# mcu2.net
KiCad netlist of a schematic drawn in Altium Designer
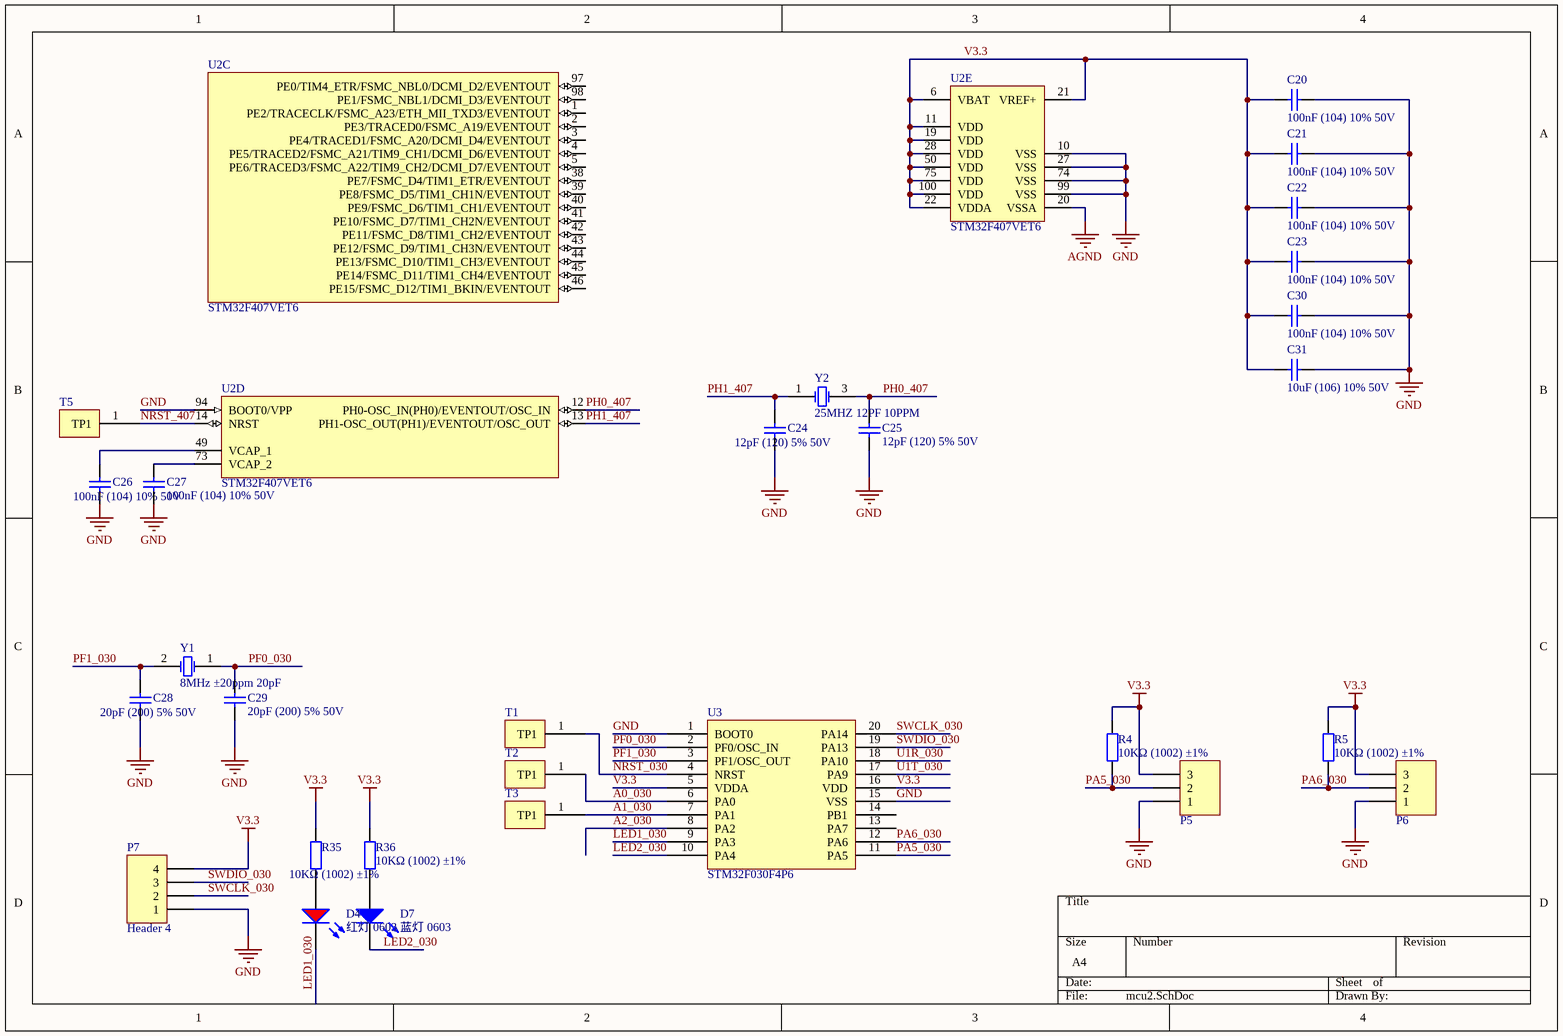
[diagram p0: mcu2.SchDoc]

(export (version "E")
  (design (tool "Eeschema 10.0.6"))
  (components
    (comp (ref "C20")
      (value "100nF (104) 10% 50V")
      (footprint "0603_C")
      (description "贴片电容")
      (libsource (lib "Miscellaneous Devices LC") (part "0603 100nF (104) 10% 50V"))
    )
    (comp (ref "C21")
      (value "100nF (104) 10% 50V")
      (footprint "0603_C")
      (description "贴片电容")
      (libsource (lib "Miscellaneous Devices LC") (part "0603 100nF (104) 10% 50V"))
    )
    (comp (ref "C22")
      (value "100nF (104) 10% 50V")
      (footprint "0603_C")
      (description "贴片电容")
      (libsource (lib "Miscellaneous Devices LC") (part "0603 100nF (104) 10% 50V"))
    )
    (comp (ref "C23")
      (value "100nF (104) 10% 50V")
      (footprint "0603_C")
      (description "贴片电容")
      (libsource (lib "Miscellaneous Devices LC") (part "0603 100nF (104) 10% 50V"))
    )
    (comp (ref "C24")
      (value "12pF (120) 5% 50V")
      (footprint "0603_C")
      (description "贴片电容")
      (libsource (lib "Miscellaneous Devices LC") (part "0603 12pF (120) 5% 50V"))
    )
    (comp (ref "C25")
      (value "12pF (120) 5% 50V")
      (footprint "0603_C")
      (description "贴片电容")
      (libsource (lib "Miscellaneous Devices LC") (part "0603 12pF (120) 5% 50V"))
    )
    (comp (ref "C26")
      (value "100nF (104) 10% 50V")
      (footprint "0603_C")
      (description "贴片电容")
      (libsource (lib "Miscellaneous Devices LC") (part "0603 100nF (104) 10% 50V"))
    )
    (comp (ref "C27")
      (value "100nF (104) 10% 50V")
      (footprint "0603_C")
      (description "贴片电容")
      (libsource (lib "Miscellaneous Devices LC") (part "0603 100nF (104) 10% 50V"))
    )
    (comp (ref "C28")
      (value "20pF (200) 5% 50V")
      (footprint "0603_C")
      (description "贴片电容")
      (libsource (lib "Miscellaneous Devices LC") (part "0603 20pF (200) 5% 50V"))
    )
    (comp (ref "C29")
      (value "20pF (200) 5% 50V")
      (footprint "0603_C")
      (description "贴片电容")
      (libsource (lib "Miscellaneous Devices LC") (part "0603 20pF (200) 5% 50V"))
    )
    (comp (ref "C30")
      (value "100nF (104) 10% 50V")
      (footprint "1206_C")
      (description "贴片电容")
      (libsource (lib "Miscellaneous Devices LC") (part "1206 100nF (104) 10% 50V"))
    )
    (comp (ref "C31")
      (value "10uF (106) 10% 50V")
      (footprint "1206_C")
      (description "贴片电容")
      (libsource (lib "Miscellaneous Devices LC") (part "1206 10uF (106) 10% 50V"))
    )
    (comp (ref "D4")
      (value "红灯 0603")
      (footprint "0603_LED_S1")
      (description "发光二极管")
      (libsource (lib "Miscellaneous Devices LC") (part "0603 红灯"))
    )
    (comp (ref "D7")
      (value "蓝灯 0603")
      (footprint "0603_LED_S1")
      (description "发光二极管")
      (libsource (lib "Miscellaneous Devices LC") (part "0603 蓝灯"))
    )
    (comp (ref "P5")
      (value "Header 3")
      (footprint "HDR1X3")
      (description "Header, 3-Pin")
      (fields (field (name "PUBLISHER") "Altium Limited"))
      (libsource (lib "Miscellaneous Connectors") (part "Header 3"))
    )
    (comp (ref "P6")
      (value "Header 3")
      (footprint "HDR1X3")
      (description "Header, 3-Pin")
      (fields (field (name "PUBLISHER") "Altium Limited"))
      (libsource (lib "Miscellaneous Connectors") (part "Header 3"))
    )
    (comp (ref "P7")
      (value "Header 4")
      (footprint "HDR1X4")
      (description "Header, 4-Pin")
      (fields (field (name "PUBLISHER") "Altium Limited"))
      (libsource (lib "Miscellaneous Connectors") (part "Header 4"))
    )
    (comp (ref "R4")
      (value "10KΩ (1002) ±1%")
      (footprint "0603_R")
      (description "贴片电阻")
      (libsource (lib "Miscellaneous Devices LC") (part "0603 10KΩ (1002) 1%"))
    )
    (comp (ref "R5")
      (value "10KΩ (1002) ±1%")
      (footprint "0603_R")
      (description "贴片电阻")
      (libsource (lib "Miscellaneous Devices LC") (part "0603 10KΩ (1002) 1%"))
    )
    (comp (ref "R35")
      (value "10KΩ (1002) ±1%")
      (footprint "0603_R")
      (description "贴片电阻")
      (libsource (lib "Miscellaneous Devices LC") (part "0603 10KΩ (1002) 1%"))
    )
    (comp (ref "R36")
      (value "10KΩ (1002) ±1%")
      (footprint "0603_R")
      (description "贴片电阻")
      (libsource (lib "Miscellaneous Devices LC") (part "0603 10KΩ (1002) 1%"))
    )
    (comp (ref "T1") (value "TP1") (footprint "TP1") (libsource (lib "CHK-I") (part "TP1")))
    (comp (ref "T2") (value "TP1") (footprint "TP1") (libsource (lib "CHK-I") (part "TP1")))
    (comp (ref "T3") (value "TP1") (footprint "TP1") (libsource (lib "CHK-I") (part "TP1")))
    (comp (ref "T5") (value "TP1") (footprint "TP1") (libsource (lib "CHK-I") (part "TP1")))
    (comp (ref "U2")
      (value "STM32F407VET6")
      (footprint "LQFP-100_14x14x05P")
      (description "ARM")
      (libsource (lib "Miscellaneous Devices LC") (part "STM32F407VET6"))
    )
    (comp (ref "U3")
      (value "STM32F030F4P6")
      (footprint "TSSOP-20")
      (description "ARM")
      (libsource (lib "Miscellaneous Devices LC") (part "STM32F030F4P6"))
    )
    (comp (ref "Y1")
      (value "8MHz ±20ppm 20pF")
      (footprint "SMD-5032_2P")
      (description "贴片晶振")
      (libsource (lib "Miscellaneous Devices LC") (part "SMD-5032_2P 8MHz 20ppm 20pF"))
    )
    (comp (ref "Y2")
      (value "25MHZ 12PF 10PPM")
      (footprint "SMD-3225_4P")
      (description "贴片晶振")
      (libsource (lib "Miscellaneous Devices LC") (part "SMD-3225_4P  25MHZ 12PF 10PPM"))
    )
  )
  (nets
    (net (code "1") (name "/A0_030") (class "Default")
      (node (ref "T2") (pin "1") (pinfunction "TP1_1") (pintype "passive"))
      (node (ref "U3") (pin "6") (pinfunction "PA0_6") (pintype "passive"))
    )
    (net (code "2") (name "/A1_030") (class "Default")
      (node (ref "T3") (pin "1") (pinfunction "TP1_1") (pintype "passive"))
      (node (ref "U3") (pin "7") (pinfunction "PA1_7") (pintype "passive"))
    )
    (net (code "3") (name "/A2_030") (class "Default")
      (node (ref "U3") (pin "8") (pinfunction "PA2_8") (pintype "passive"))
    )
    (net (code "4") (name "/LED1_030") (class "Default")
      (node (ref "D4") (pin "K") (pinfunction "K_K") (pintype "passive"))
      (node (ref "U3") (pin "9") (pinfunction "PA3_9") (pintype "passive"))
    )
    (net (code "5") (name "/LED2_030") (class "Default")
      (node (ref "D7") (pin "K") (pinfunction "K_K") (pintype "passive"))
      (node (ref "U3") (pin "10") (pinfunction "PA4_10") (pintype "passive"))
    )
    (net (code "6") (name "/NRST_030") (class "Default")
      (node (ref "T1") (pin "1") (pinfunction "TP1_1") (pintype "passive"))
      (node (ref "U3") (pin "4") (pinfunction "NRST_4") (pintype "passive"))
    )
    (net (code "7") (name "/NRST_407") (class "Default")
      (node (ref "T5") (pin "1") (pinfunction "TP1_1") (pintype "passive"))
      (node (ref "U2") (pin "14") (pinfunction "NRST_14") (pintype "bidirectional"))
    )
    (net (code "8") (name "/PA5_030") (class "Default")
      (node (ref "P5") (pin "2") (pinfunction "2_2") (pintype "passive"))
      (node (ref "R4") (pin "1") (pinfunction "1_1") (pintype "passive"))
      (node (ref "U3") (pin "11") (pinfunction "PA5_11") (pintype "passive"))
    )
    (net (code "9") (name "/PA6_030") (class "Default")
      (node (ref "P6") (pin "2") (pinfunction "2_2") (pintype "passive"))
      (node (ref "R5") (pin "1") (pinfunction "1_1") (pintype "passive"))
      (node (ref "U3") (pin "12") (pinfunction "PA6_12") (pintype "passive"))
    )
    (net (code "10") (name "/PF0_030") (class "Default")
      (node (ref "C29") (pin "2") (pinfunction "2_2") (pintype "passive"))
      (node (ref "U3") (pin "2") (pinfunction "PF0/OSC_IN_2") (pintype "passive"))
      (node (ref "Y1") (pin "1") (pinfunction "OSC1_1") (pintype "passive"))
    )
    (net (code "11") (name "/PF1_030") (class "Default")
      (node (ref "C28") (pin "2") (pinfunction "2_2") (pintype "passive"))
      (node (ref "U3") (pin "3") (pinfunction "PF1/OSC_OUT_3") (pintype "passive"))
      (node (ref "Y1") (pin "2") (pinfunction "OSC2_2") (pintype "passive"))
    )
    (net (code "12") (name "/PH0_407") (class "Default")
      (node (ref "C25") (pin "2") (pinfunction "2_2") (pintype "passive"))
      (node (ref "U2") (pin "12") (pinfunction "PH0-OSC_IN(PH0)/EVENTOUT/OSC_IN_12") (pintype "bidirectional"))
      (node (ref "Y2") (pin "3") (pinfunction "OSC2_3") (pintype "passive"))
    )
    (net (code "13") (name "/PH1_407") (class "Default")
      (node (ref "C24") (pin "2") (pinfunction "2_2") (pintype "passive"))
      (node (ref "U2") (pin "13") (pinfunction "PH1-OSC_OUT(PH1)/EVENTOUT/OSC_OUT_13") (pintype "bidirectional"))
      (node (ref "Y2") (pin "1") (pinfunction "OSC1_1") (pintype "passive"))
    )
    (net (code "14") (name "/SWCLK_030") (class "Default")
      (node (ref "P7") (pin "2") (pinfunction "2_2") (pintype "passive"))
      (node (ref "U3") (pin "20") (pinfunction "PA14_20") (pintype "passive"))
    )
    (net (code "15") (name "/SWDIO_030") (class "Default")
      (node (ref "P7") (pin "3") (pinfunction "3_3") (pintype "passive"))
      (node (ref "U3") (pin "19") (pinfunction "PA13_19") (pintype "passive"))
    )
    (net (code "16") (name "/U1R_030") (class "Default")
      (node (ref "U3") (pin "18") (pinfunction "PA10_18") (pintype "passive"))
    )
    (net (code "17") (name "/U1T_030") (class "Default")
      (node (ref "U3") (pin "17") (pinfunction "PA9_17") (pintype "passive"))
    )
    (net (code "18") (name "AGND") (class "Default")
      (node (ref "U2") (pin "20") (pinfunction "VSSA_20") (pintype "power_in"))
    )
    (net (code "19") (name "GND") (class "Default")
      (node (ref "C20") (pin "2") (pinfunction "2_2") (pintype "passive"))
      (node (ref "C21") (pin "2") (pinfunction "2_2") (pintype "passive"))
      (node (ref "C22") (pin "2") (pinfunction "2_2") (pintype "passive"))
      (node (ref "C23") (pin "2") (pinfunction "2_2") (pintype "passive"))
      (node (ref "C24") (pin "1") (pinfunction "1_1") (pintype "passive"))
      (node (ref "C25") (pin "1") (pinfunction "1_1") (pintype "passive"))
      (node (ref "C26") (pin "1") (pinfunction "1_1") (pintype "passive"))
      (node (ref "C27") (pin "1") (pinfunction "1_1") (pintype "passive"))
      (node (ref "C28") (pin "1") (pinfunction "1_1") (pintype "passive"))
      (node (ref "C29") (pin "1") (pinfunction "1_1") (pintype "passive"))
      (node (ref "C30") (pin "2") (pinfunction "2_2") (pintype "passive"))
      (node (ref "C31") (pin "2") (pinfunction "2_2") (pintype "passive"))
      (node (ref "P5") (pin "1") (pinfunction "1_1") (pintype "passive"))
      (node (ref "P6") (pin "1") (pinfunction "1_1") (pintype "passive"))
      (node (ref "P7") (pin "1") (pinfunction "1_1") (pintype "passive"))
      (node (ref "U2") (pin "10") (pinfunction "VSS_10") (pintype "power_in"))
      (node (ref "U2") (pin "27") (pinfunction "VSS_27") (pintype "power_in"))
      (node (ref "U2") (pin "74") (pinfunction "VSS_74") (pintype "power_in"))
      (node (ref "U2") (pin "94") (pinfunction "BOOT0/VPP_94") (pintype "input"))
      (node (ref "U2") (pin "99") (pinfunction "VSS_99") (pintype "power_in"))
      (node (ref "U3") (pin "1") (pinfunction "BOOT0_1") (pintype "passive"))
      (node (ref "U3") (pin "15") (pinfunction "VSS_15") (pintype "passive"))
    )
    (net (code "20") (name "Net-(D4-PadA)") (class "Default")
      (node (ref "D4") (pin "A") (pinfunction "A_A") (pintype "passive"))
      (node (ref "R35") (pin "1") (pinfunction "1_1") (pintype "passive"))
    )
    (net (code "21") (name "Net-(D7-PadA)") (class "Default")
      (node (ref "D7") (pin "A") (pinfunction "A_A") (pintype "passive"))
      (node (ref "R36") (pin "1") (pinfunction "1_1") (pintype "passive"))
    )
    (net (code "22") (name "Net-(U2D-VCAP_1)") (class "Default")
      (node (ref "C26") (pin "2") (pinfunction "2_2") (pintype "passive"))
      (node (ref "U2") (pin "49") (pinfunction "VCAP_1_49") (pintype "power_in"))
    )
    (net (code "23") (name "Net-(U2D-VCAP_2)") (class "Default")
      (node (ref "C27") (pin "2") (pinfunction "2_2") (pintype "passive"))
      (node (ref "U2") (pin "73") (pinfunction "VCAP_2_73") (pintype "power_in"))
    )
    (net (code "24") (name "V3.3") (class "Default")
      (node (ref "C20") (pin "1") (pinfunction "1_1") (pintype "passive"))
      (node (ref "C21") (pin "1") (pinfunction "1_1") (pintype "passive"))
      (node (ref "C22") (pin "1") (pinfunction "1_1") (pintype "passive"))
      (node (ref "C23") (pin "1") (pinfunction "1_1") (pintype "passive"))
      (node (ref "C30") (pin "1") (pinfunction "1_1") (pintype "passive"))
      (node (ref "C31") (pin "1") (pinfunction "1_1") (pintype "passive"))
      (node (ref "P5") (pin "3") (pinfunction "3_3") (pintype "passive"))
      (node (ref "P6") (pin "3") (pinfunction "3_3") (pintype "passive"))
      (node (ref "P7") (pin "4") (pinfunction "4_4") (pintype "passive"))
      (node (ref "R35") (pin "2") (pinfunction "2_2") (pintype "passive"))
      (node (ref "R36") (pin "2") (pinfunction "2_2") (pintype "passive"))
      (node (ref "R4") (pin "2") (pinfunction "2_2") (pintype "passive"))
      (node (ref "R5") (pin "2") (pinfunction "2_2") (pintype "passive"))
      (node (ref "U2") (pin "100") (pinfunction "VDD_100") (pintype "power_in"))
      (node (ref "U2") (pin "11") (pinfunction "VDD_11") (pintype "power_in"))
      (node (ref "U2") (pin "19") (pinfunction "VDD_19") (pintype "power_in"))
      (node (ref "U2") (pin "21") (pinfunction "VREF+_21") (pintype "power_in"))
      (node (ref "U2") (pin "22") (pinfunction "VDDA_22") (pintype "power_in"))
      (node (ref "U2") (pin "28") (pinfunction "VDD_28") (pintype "power_in"))
      (node (ref "U2") (pin "50") (pinfunction "VDD_50") (pintype "power_in"))
      (node (ref "U2") (pin "6") (pinfunction "VBAT_6") (pintype "power_in"))
      (node (ref "U2") (pin "75") (pinfunction "VDD_75") (pintype "power_in"))
      (node (ref "U3") (pin "16") (pinfunction "VDD_16") (pintype "passive"))
      (node (ref "U3") (pin "5") (pinfunction "VDDA_5") (pintype "passive"))
    )
    (net (code "25") (name "unconnected-(U2C-PE0{slash}TIM4_ETR{slash}FSMC_NBL0{slash}DCMI_D2{slash}EVENTOUT-Pad97)") (class "Default")
      (node (ref "U2") (pin "97") (pinfunction "PE0/TIM4_ETR/FSMC_NBL0/DCMI_D2/EVENTOUT_97") (pintype "bidirectional"))
    )
    (net (code "26") (name "unconnected-(U2C-PE1{slash}FSMC_NBL1{slash}DCMI_D3{slash}EVENTOUT-Pad98)") (class "Default")
      (node (ref "U2") (pin "98") (pinfunction "PE1/FSMC_NBL1/DCMI_D3/EVENTOUT_98") (pintype "bidirectional"))
    )
    (net (code "27") (name "unconnected-(U2C-PE2{slash}TRACECLK{slash}FSMC_A23{slash}ETH_MII_TXD3{slash}EVENTOUT-Pad1)") (class "Default")
      (node (ref "U2") (pin "1") (pinfunction "PE2/TRACECLK/FSMC_A23/ETH_MII_TXD3/EVENTOUT_1") (pintype "bidirectional"))
    )
    (net (code "28") (name "unconnected-(U2C-PE3{slash}TRACED0{slash}FSMC_A19{slash}EVENTOUT-Pad2)") (class "Default")
      (node (ref "U2") (pin "2") (pinfunction "PE3/TRACED0/FSMC_A19/EVENTOUT_2") (pintype "bidirectional"))
    )
    (net (code "29") (name "unconnected-(U2C-PE4{slash}TRACED1{slash}FSMC_A20{slash}DCMI_D4{slash}EVENTOUT-Pad3)") (class "Default")
      (node (ref "U2") (pin "3") (pinfunction "PE4/TRACED1/FSMC_A20/DCMI_D4/EVENTOUT_3") (pintype "bidirectional"))
    )
    (net (code "30") (name "unconnected-(U2C-PE5{slash}TRACED2{slash}FSMC_A21{slash}TIM9_CH1{slash}DCMI_D6{slash}EVENTOUT-Pad4)") (class "Default")
      (node (ref "U2") (pin "4") (pinfunction "PE5/TRACED2/FSMC_A21/TIM9_CH1/DCMI_D6/EVENTOUT_4") (pintype "bidirectional"))
    )
    (net (code "31") (name "unconnected-(U2C-PE6{slash}TRACED3{slash}FSMC_A22{slash}TIM9_CH2{slash}DCMI_D7{slash}EVENTOUT-Pad5)") (class "Default")
      (node (ref "U2") (pin "5") (pinfunction "PE6/TRACED3/FSMC_A22/TIM9_CH2/DCMI_D7/EVENTOUT_5") (pintype "bidirectional"))
    )
    (net (code "32") (name "unconnected-(U2C-PE7{slash}FSMC_D4{slash}TIM1_ETR{slash}EVENTOUT-Pad38)") (class "Default")
      (node (ref "U2") (pin "38") (pinfunction "PE7/FSMC_D4/TIM1_ETR/EVENTOUT_38") (pintype "bidirectional"))
    )
    (net (code "33") (name "unconnected-(U2C-PE8{slash}FSMC_D5{slash}TIM1_CH1N{slash}EVENTOUT-Pad39)") (class "Default")
      (node (ref "U2") (pin "39") (pinfunction "PE8/FSMC_D5/TIM1_CH1N/EVENTOUT_39") (pintype "bidirectional"))
    )
    (net (code "34") (name "unconnected-(U2C-PE9{slash}FSMC_D6{slash}TIM1_CH1{slash}EVENTOUT-Pad40)") (class "Default")
      (node (ref "U2") (pin "40") (pinfunction "PE9/FSMC_D6/TIM1_CH1/EVENTOUT_40") (pintype "bidirectional"))
    )
    (net (code "35") (name "unconnected-(U2C-PE10{slash}FSMC_D7{slash}TIM1_CH2N{slash}EVENTOUT-Pad41)") (class "Default")
      (node (ref "U2") (pin "41") (pinfunction "PE10/FSMC_D7/TIM1_CH2N/EVENTOUT_41") (pintype "bidirectional"))
    )
    (net (code "36") (name "unconnected-(U2C-PE11{slash}FSMC_D8{slash}TIM1_CH2{slash}EVENTOUT-Pad42)") (class "Default")
      (node (ref "U2") (pin "42") (pinfunction "PE11/FSMC_D8/TIM1_CH2/EVENTOUT_42") (pintype "bidirectional"))
    )
    (net (code "37") (name "unconnected-(U2C-PE12{slash}FSMC_D9{slash}TIM1_CH3N{slash}EVENTOUT-Pad43)") (class "Default")
      (node (ref "U2") (pin "43") (pinfunction "PE12/FSMC_D9/TIM1_CH3N/EVENTOUT_43") (pintype "bidirectional"))
    )
    (net (code "38") (name "unconnected-(U2C-PE13{slash}FSMC_D10{slash}TIM1_CH3{slash}EVENTOUT-Pad44)") (class "Default")
      (node (ref "U2") (pin "44") (pinfunction "PE13/FSMC_D10/TIM1_CH3/EVENTOUT_44") (pintype "bidirectional"))
    )
    (net (code "39") (name "unconnected-(U2C-PE14{slash}FSMC_D11{slash}TIM1_CH4{slash}EVENTOUT-Pad45)") (class "Default")
      (node (ref "U2") (pin "45") (pinfunction "PE14/FSMC_D11/TIM1_CH4/EVENTOUT_45") (pintype "bidirectional"))
    )
    (net (code "40") (name "unconnected-(U2C-PE15{slash}FSMC_D12{slash}TIM1_BKIN{slash}EVENTOUT-Pad46)") (class "Default")
      (node (ref "U2") (pin "46") (pinfunction "PE15/FSMC_D12/TIM1_BKIN/EVENTOUT_46") (pintype "bidirectional"))
    )
    (net (code "41") (name "unconnected-(U3-PA7-Pad13)") (class "Default")
      (node (ref "U3") (pin "13") (pinfunction "PA7_13") (pintype "passive"))
    )
    (net (code "42") (name "unconnected-(U3-PB1-Pad14)") (class "Default")
      (node (ref "U3") (pin "14") (pinfunction "PB1_14") (pintype "passive"))
    )
  )
)
